# uBraids_SE_Display_Module.net
KiCad netlist of a schematic drawn in EAGLE
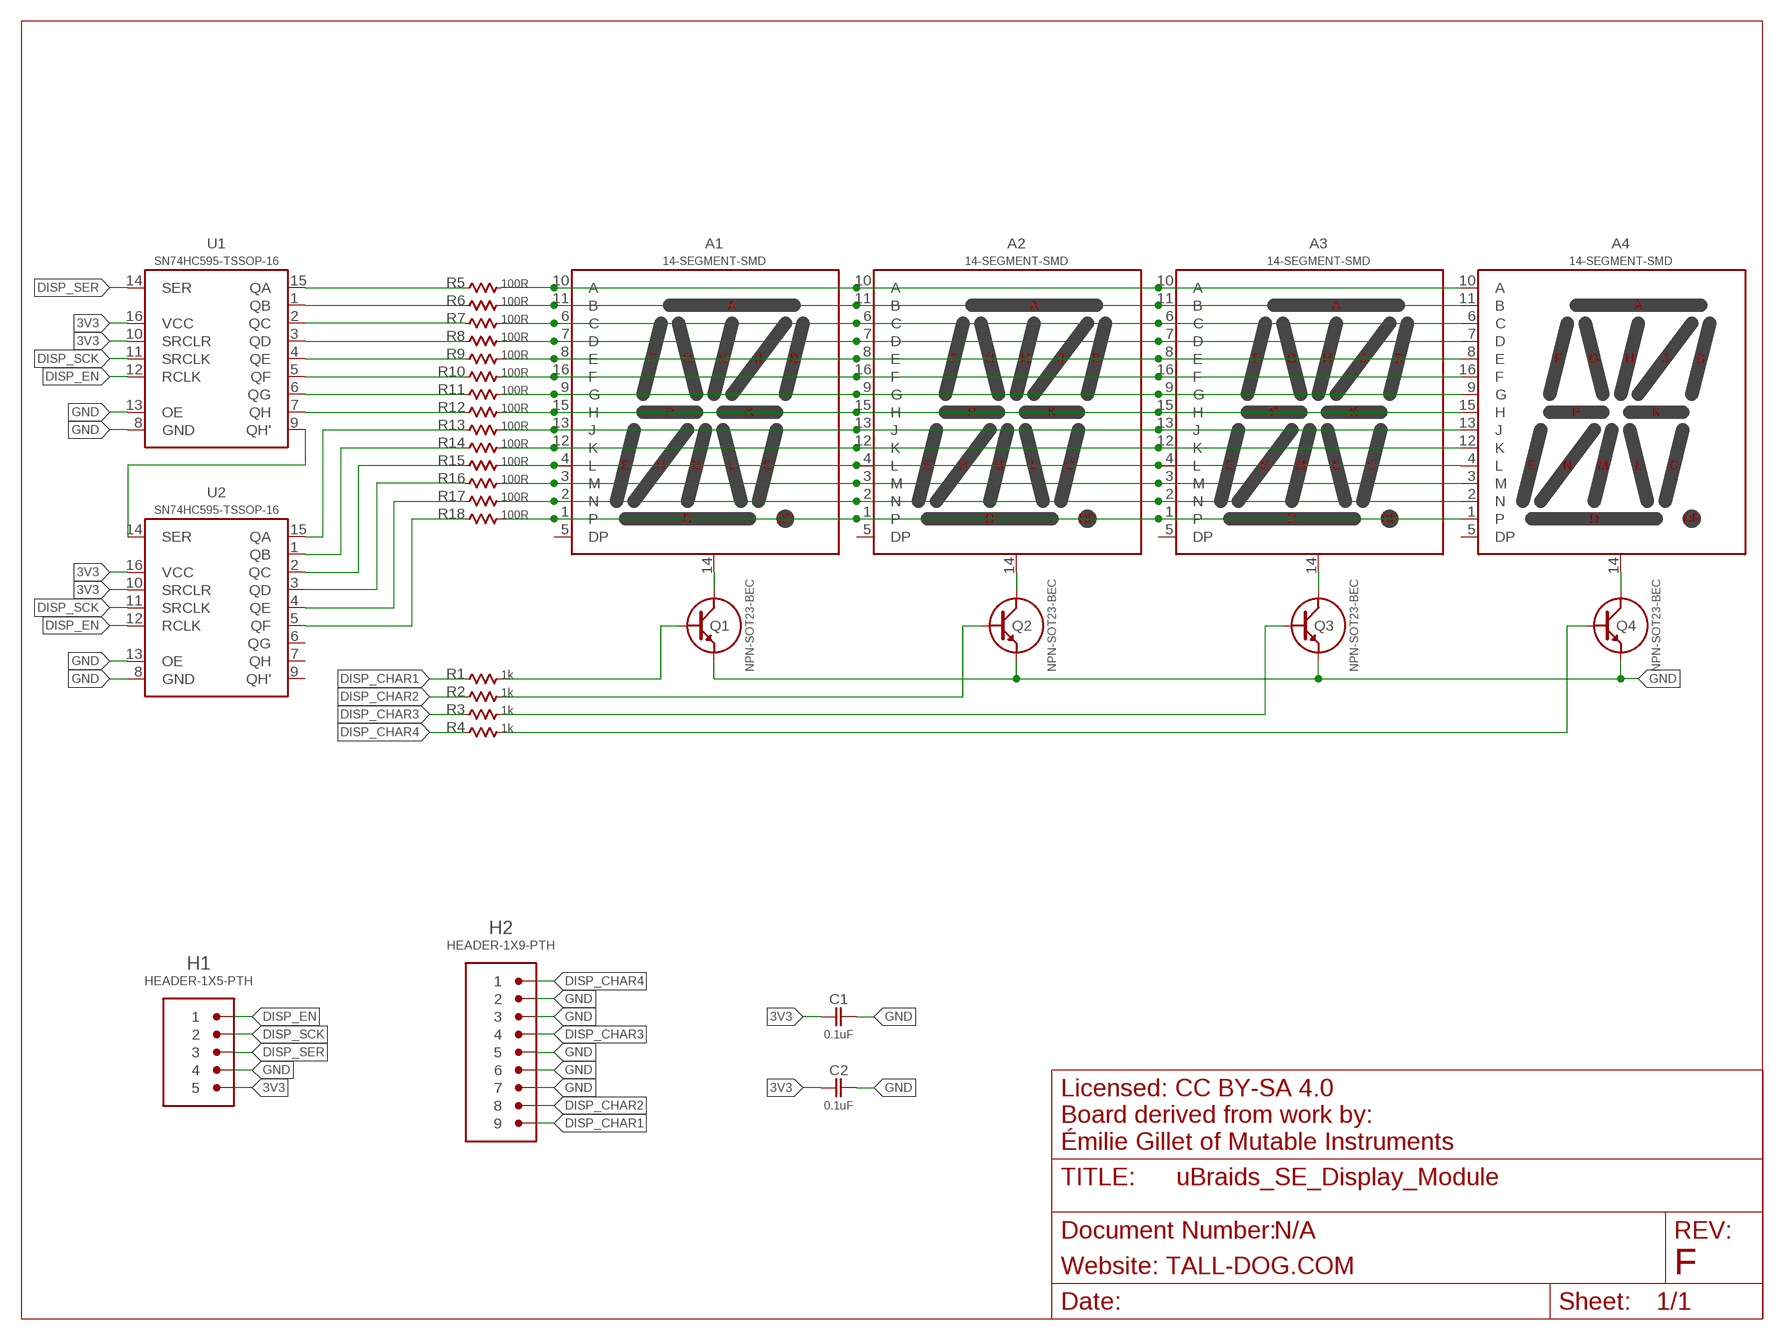
[diagram p0: schematic, sheet 1]

(export (version "E")
  (design (tool "Eeschema 10.0.6"))
  (components
    (comp (ref "A1")
      (value "14-SEGMENT-SMD")
      (footprint "eagle-import:14-SEGMENT")
      (libsource (lib "eagle-import") (part "14-SEGMENT-SMD"))
    )
    (comp (ref "A2")
      (value "14-SEGMENT-SMD")
      (footprint "eagle-import:14-SEGMENT")
      (libsource (lib "eagle-import") (part "14-SEGMENT-SMD"))
    )
    (comp (ref "A3")
      (value "14-SEGMENT-SMD")
      (footprint "eagle-import:14-SEGMENT")
      (libsource (lib "eagle-import") (part "14-SEGMENT-SMD"))
    )
    (comp (ref "A4")
      (value "14-SEGMENT-SMD")
      (footprint "eagle-import:14-SEGMENT")
      (libsource (lib "eagle-import") (part "14-SEGMENT-SMD"))
    )
    (comp (ref "C1")
      (value "0.1uF")
      (footprint "eagle-import:0603-NP")
      (libsource (lib "eagle-import") (part "CAP-NP-0603"))
    )
    (comp (ref "C2")
      (value "0.1uF")
      (footprint "eagle-import:0603-NP")
      (libsource (lib "eagle-import") (part "CAP-NP-0603"))
    )
    (comp (ref "H1")
      (value "HEADER-1X5-PTH")
      (footprint "eagle-import:PTH-0.1-1X5")
      (libsource (lib "eagle-import") (part "HEADER-1X5-PTH"))
    )
    (comp (ref "H2")
      (value "HEADER-1X9-PTH")
      (footprint "eagle-import:PTH-0.1-1X9")
      (libsource (lib "eagle-import") (part "HEADER-1X9-PTH"))
    )
    (comp (ref "Q1")
      (value "NPN-SOT23-BEC")
      (footprint "eagle-import:SOT-23")
      (libsource (lib "eagle-import") (part "NPN-SOT23-BEC"))
    )
    (comp (ref "Q2")
      (value "NPN-SOT23-BEC")
      (footprint "eagle-import:SOT-23")
      (libsource (lib "eagle-import") (part "NPN-SOT23-BEC"))
    )
    (comp (ref "Q3")
      (value "NPN-SOT23-BEC")
      (footprint "eagle-import:SOT-23")
      (libsource (lib "eagle-import") (part "NPN-SOT23-BEC"))
    )
    (comp (ref "Q4")
      (value "NPN-SOT23-BEC")
      (footprint "eagle-import:SOT-23")
      (libsource (lib "eagle-import") (part "NPN-SOT23-BEC"))
    )
    (comp (ref "R1")
      (value "1k")
      (footprint "eagle-import:0603-NP")
      (libsource (lib "eagle-import") (part "RESISTOR-0603"))
    )
    (comp (ref "R2")
      (value "1k")
      (footprint "eagle-import:0603-NP")
      (libsource (lib "eagle-import") (part "RESISTOR-0603"))
    )
    (comp (ref "R3")
      (value "1k")
      (footprint "eagle-import:0603-NP")
      (libsource (lib "eagle-import") (part "RESISTOR-0603"))
    )
    (comp (ref "R4")
      (value "1k")
      (footprint "eagle-import:0603-NP")
      (libsource (lib "eagle-import") (part "RESISTOR-0603"))
    )
    (comp (ref "R5")
      (value "100R")
      (footprint "eagle-import:0603-NP")
      (libsource (lib "eagle-import") (part "RESISTOR-0603"))
    )
    (comp (ref "R6")
      (value "100R")
      (footprint "eagle-import:0603-NP")
      (libsource (lib "eagle-import") (part "RESISTOR-0603"))
    )
    (comp (ref "R7")
      (value "100R")
      (footprint "eagle-import:0603-NP")
      (libsource (lib "eagle-import") (part "RESISTOR-0603"))
    )
    (comp (ref "R8")
      (value "100R")
      (footprint "eagle-import:0603-NP")
      (libsource (lib "eagle-import") (part "RESISTOR-0603"))
    )
    (comp (ref "R9")
      (value "100R")
      (footprint "eagle-import:0603-NP")
      (libsource (lib "eagle-import") (part "RESISTOR-0603"))
    )
    (comp (ref "R10")
      (value "100R")
      (footprint "eagle-import:0603-NP")
      (libsource (lib "eagle-import") (part "RESISTOR-0603"))
    )
    (comp (ref "R11")
      (value "100R")
      (footprint "eagle-import:0603-NP")
      (libsource (lib "eagle-import") (part "RESISTOR-0603"))
    )
    (comp (ref "R12")
      (value "100R")
      (footprint "eagle-import:0603-NP")
      (libsource (lib "eagle-import") (part "RESISTOR-0603"))
    )
    (comp (ref "R13")
      (value "100R")
      (footprint "eagle-import:0603-NP")
      (libsource (lib "eagle-import") (part "RESISTOR-0603"))
    )
    (comp (ref "R14")
      (value "100R")
      (footprint "eagle-import:0603-NP")
      (libsource (lib "eagle-import") (part "RESISTOR-0603"))
    )
    (comp (ref "R15")
      (value "100R")
      (footprint "eagle-import:0603-NP")
      (libsource (lib "eagle-import") (part "RESISTOR-0603"))
    )
    (comp (ref "R16")
      (value "100R")
      (footprint "eagle-import:0603-NP")
      (libsource (lib "eagle-import") (part "RESISTOR-0603"))
    )
    (comp (ref "R17")
      (value "100R")
      (footprint "eagle-import:0603-NP")
      (libsource (lib "eagle-import") (part "RESISTOR-0603"))
    )
    (comp (ref "R18")
      (value "100R")
      (footprint "eagle-import:0603-NP")
      (libsource (lib "eagle-import") (part "RESISTOR-0603"))
    )
    (comp (ref "U1")
      (value "SN74HC595-TSSOP-16")
      (footprint "eagle-import:TSSOP-16")
      (libsource (lib "eagle-import") (part "SN74HC595-TSSOP-16"))
    )
    (comp (ref "U2")
      (value "SN74HC595-TSSOP-16")
      (footprint "eagle-import:TSSOP-16")
      (libsource (lib "eagle-import") (part "SN74HC595-TSSOP-16"))
    )
  )
  (nets
    (net (code "1") (name "3V3") (class "Default")
      (node (ref "C1") (pin "1") (pinfunction "1_1") (pintype "bidirectional"))
      (node (ref "C2") (pin "1") (pinfunction "1_1") (pintype "bidirectional"))
      (node (ref "H1") (pin "5") (pinfunction "5_5") (pintype "bidirectional"))
      (node (ref "U1") (pin "10") (pinfunction "SRCLR_10") (pintype "bidirectional"))
      (node (ref "U1") (pin "16") (pinfunction "VCC_16") (pintype "bidirectional"))
      (node (ref "U2") (pin "10") (pinfunction "SRCLR_10") (pintype "bidirectional"))
      (node (ref "U2") (pin "16") (pinfunction "VCC_16") (pintype "bidirectional"))
    )
    (net (code "2") (name "DISP_CHAR1") (class "Default")
      (node (ref "H2") (pin "9") (pinfunction "9_9") (pintype "bidirectional"))
      (node (ref "R1") (pin "1") (pinfunction "1_1") (pintype "passive"))
    )
    (net (code "3") (name "DISP_CHAR2") (class "Default")
      (node (ref "H2") (pin "8") (pinfunction "8_8") (pintype "bidirectional"))
      (node (ref "R2") (pin "1") (pinfunction "1_1") (pintype "passive"))
    )
    (net (code "4") (name "DISP_CHAR3") (class "Default")
      (node (ref "H2") (pin "4") (pinfunction "4_4") (pintype "bidirectional"))
      (node (ref "R3") (pin "1") (pinfunction "1_1") (pintype "passive"))
    )
    (net (code "5") (name "DISP_CHAR4") (class "Default")
      (node (ref "H2") (pin "1") (pinfunction "1_1") (pintype "bidirectional"))
      (node (ref "R4") (pin "1") (pinfunction "1_1") (pintype "passive"))
    )
    (net (code "6") (name "DISP_EN") (class "Default")
      (node (ref "H1") (pin "1") (pinfunction "1_1") (pintype "bidirectional"))
      (node (ref "U1") (pin "12") (pinfunction "RCLK_12") (pintype "bidirectional"))
      (node (ref "U2") (pin "12") (pinfunction "RCLK_12") (pintype "bidirectional"))
    )
    (net (code "7") (name "DISP_SCK") (class "Default")
      (node (ref "H1") (pin "2") (pinfunction "2_2") (pintype "bidirectional"))
      (node (ref "U1") (pin "11") (pinfunction "SRCLK_11") (pintype "bidirectional"))
      (node (ref "U2") (pin "11") (pinfunction "SRCLK_11") (pintype "bidirectional"))
    )
    (net (code "8") (name "DISP_SER") (class "Default")
      (node (ref "H1") (pin "3") (pinfunction "3_3") (pintype "bidirectional"))
      (node (ref "U1") (pin "14") (pinfunction "SER_14") (pintype "bidirectional"))
    )
    (net (code "9") (name "GND") (class "Default")
      (node (ref "C1") (pin "2") (pinfunction "2_2") (pintype "bidirectional"))
      (node (ref "C2") (pin "2") (pinfunction "2_2") (pintype "bidirectional"))
      (node (ref "H1") (pin "4") (pinfunction "4_4") (pintype "bidirectional"))
      (node (ref "H2") (pin "2") (pinfunction "2_2") (pintype "bidirectional"))
      (node (ref "H2") (pin "3") (pinfunction "3_3") (pintype "bidirectional"))
      (node (ref "H2") (pin "5") (pinfunction "5_5") (pintype "bidirectional"))
      (node (ref "H2") (pin "6") (pinfunction "6_6") (pintype "bidirectional"))
      (node (ref "H2") (pin "7") (pinfunction "7_7") (pintype "bidirectional"))
      (node (ref "Q1") (pin "2") (pinfunction "E_2") (pintype "passive"))
      (node (ref "Q2") (pin "2") (pinfunction "E_2") (pintype "passive"))
      (node (ref "Q3") (pin "2") (pinfunction "E_2") (pintype "passive"))
      (node (ref "Q4") (pin "2") (pinfunction "E_2") (pintype "passive"))
      (node (ref "U1") (pin "13") (pinfunction "OE_13") (pintype "bidirectional"))
      (node (ref "U1") (pin "8") (pinfunction "GND_8") (pintype "bidirectional"))
      (node (ref "U2") (pin "13") (pinfunction "OE_13") (pintype "bidirectional"))
      (node (ref "U2") (pin "8") (pinfunction "GND_8") (pintype "bidirectional"))
    )
    (net (code "10") (name "Net-(A1-A)") (class "Default")
      (node (ref "A1") (pin "10") (pinfunction "A_10") (pintype "bidirectional"))
      (node (ref "A2") (pin "10") (pinfunction "A_10") (pintype "bidirectional"))
      (node (ref "A3") (pin "10") (pinfunction "A_10") (pintype "bidirectional"))
      (node (ref "A4") (pin "10") (pinfunction "A_10") (pintype "bidirectional"))
      (node (ref "R5") (pin "2") (pinfunction "2_2") (pintype "passive"))
    )
    (net (code "11") (name "Net-(A1-B)") (class "Default")
      (node (ref "A1") (pin "11") (pinfunction "B_11") (pintype "bidirectional"))
      (node (ref "A2") (pin "11") (pinfunction "B_11") (pintype "bidirectional"))
      (node (ref "A3") (pin "11") (pinfunction "B_11") (pintype "bidirectional"))
      (node (ref "A4") (pin "11") (pinfunction "B_11") (pintype "bidirectional"))
      (node (ref "R6") (pin "2") (pinfunction "2_2") (pintype "passive"))
    )
    (net (code "12") (name "Net-(A1-C)") (class "Default")
      (node (ref "A1") (pin "6") (pinfunction "C_6") (pintype "bidirectional"))
      (node (ref "A2") (pin "6") (pinfunction "C_6") (pintype "bidirectional"))
      (node (ref "A3") (pin "6") (pinfunction "C_6") (pintype "bidirectional"))
      (node (ref "A4") (pin "6") (pinfunction "C_6") (pintype "bidirectional"))
      (node (ref "R7") (pin "2") (pinfunction "2_2") (pintype "passive"))
    )
    (net (code "13") (name "Net-(A1-CATHODE)") (class "Default")
      (node (ref "A1") (pin "14") (pinfunction "CATHODE_14") (pintype "bidirectional"))
      (node (ref "Q1") (pin "3") (pinfunction "C_3") (pintype "passive"))
    )
    (net (code "14") (name "Net-(A1-D)") (class "Default")
      (node (ref "A1") (pin "7") (pinfunction "D_7") (pintype "bidirectional"))
      (node (ref "A2") (pin "7") (pinfunction "D_7") (pintype "bidirectional"))
      (node (ref "A3") (pin "7") (pinfunction "D_7") (pintype "bidirectional"))
      (node (ref "A4") (pin "7") (pinfunction "D_7") (pintype "bidirectional"))
      (node (ref "R8") (pin "2") (pinfunction "2_2") (pintype "passive"))
    )
    (net (code "15") (name "Net-(A1-E)") (class "Default")
      (node (ref "A1") (pin "8") (pinfunction "E_8") (pintype "bidirectional"))
      (node (ref "A2") (pin "8") (pinfunction "E_8") (pintype "bidirectional"))
      (node (ref "A3") (pin "8") (pinfunction "E_8") (pintype "bidirectional"))
      (node (ref "A4") (pin "8") (pinfunction "E_8") (pintype "bidirectional"))
      (node (ref "R9") (pin "2") (pinfunction "2_2") (pintype "passive"))
    )
    (net (code "16") (name "Net-(A1-F)") (class "Default")
      (node (ref "A1") (pin "16") (pinfunction "F_16") (pintype "bidirectional"))
      (node (ref "A2") (pin "16") (pinfunction "F_16") (pintype "bidirectional"))
      (node (ref "A3") (pin "16") (pinfunction "F_16") (pintype "bidirectional"))
      (node (ref "A4") (pin "16") (pinfunction "F_16") (pintype "bidirectional"))
      (node (ref "R10") (pin "2") (pinfunction "2_2") (pintype "passive"))
    )
    (net (code "17") (name "Net-(A1-G)") (class "Default")
      (node (ref "A1") (pin "9") (pinfunction "G_9") (pintype "bidirectional"))
      (node (ref "A2") (pin "9") (pinfunction "G_9") (pintype "bidirectional"))
      (node (ref "A3") (pin "9") (pinfunction "G_9") (pintype "bidirectional"))
      (node (ref "A4") (pin "9") (pinfunction "G_9") (pintype "bidirectional"))
      (node (ref "R11") (pin "2") (pinfunction "2_2") (pintype "passive"))
    )
    (net (code "18") (name "Net-(A1-H)") (class "Default")
      (node (ref "A1") (pin "15") (pinfunction "H_15") (pintype "bidirectional"))
      (node (ref "A2") (pin "15") (pinfunction "H_15") (pintype "bidirectional"))
      (node (ref "A3") (pin "15") (pinfunction "H_15") (pintype "bidirectional"))
      (node (ref "A4") (pin "15") (pinfunction "H_15") (pintype "bidirectional"))
      (node (ref "R12") (pin "2") (pinfunction "2_2") (pintype "passive"))
    )
    (net (code "19") (name "Net-(A1-J)") (class "Default")
      (node (ref "A1") (pin "13") (pinfunction "J_13") (pintype "bidirectional"))
      (node (ref "A2") (pin "13") (pinfunction "J_13") (pintype "bidirectional"))
      (node (ref "A3") (pin "13") (pinfunction "J_13") (pintype "bidirectional"))
      (node (ref "A4") (pin "13") (pinfunction "J_13") (pintype "bidirectional"))
      (node (ref "R13") (pin "2") (pinfunction "2_2") (pintype "passive"))
    )
    (net (code "20") (name "Net-(A1-K)") (class "Default")
      (node (ref "A1") (pin "12") (pinfunction "K_12") (pintype "bidirectional"))
      (node (ref "A2") (pin "12") (pinfunction "K_12") (pintype "bidirectional"))
      (node (ref "A3") (pin "12") (pinfunction "K_12") (pintype "bidirectional"))
      (node (ref "A4") (pin "12") (pinfunction "K_12") (pintype "bidirectional"))
      (node (ref "R14") (pin "2") (pinfunction "2_2") (pintype "passive"))
    )
    (net (code "21") (name "Net-(A1-L)") (class "Default")
      (node (ref "A1") (pin "4") (pinfunction "L_4") (pintype "bidirectional"))
      (node (ref "A2") (pin "4") (pinfunction "L_4") (pintype "bidirectional"))
      (node (ref "A3") (pin "4") (pinfunction "L_4") (pintype "bidirectional"))
      (node (ref "A4") (pin "4") (pinfunction "L_4") (pintype "bidirectional"))
      (node (ref "R15") (pin "2") (pinfunction "2_2") (pintype "passive"))
    )
    (net (code "22") (name "Net-(A1-M)") (class "Default")
      (node (ref "A1") (pin "3") (pinfunction "M_3") (pintype "bidirectional"))
      (node (ref "A2") (pin "3") (pinfunction "M_3") (pintype "bidirectional"))
      (node (ref "A3") (pin "3") (pinfunction "M_3") (pintype "bidirectional"))
      (node (ref "A4") (pin "3") (pinfunction "M_3") (pintype "bidirectional"))
      (node (ref "R16") (pin "2") (pinfunction "2_2") (pintype "passive"))
    )
    (net (code "23") (name "Net-(A1-N)") (class "Default")
      (node (ref "A1") (pin "2") (pinfunction "N_2") (pintype "bidirectional"))
      (node (ref "A2") (pin "2") (pinfunction "N_2") (pintype "bidirectional"))
      (node (ref "A3") (pin "2") (pinfunction "N_2") (pintype "bidirectional"))
      (node (ref "A4") (pin "2") (pinfunction "N_2") (pintype "bidirectional"))
      (node (ref "R17") (pin "2") (pinfunction "2_2") (pintype "passive"))
    )
    (net (code "24") (name "Net-(A1-P)") (class "Default")
      (node (ref "A1") (pin "1") (pinfunction "P_1") (pintype "bidirectional"))
      (node (ref "A2") (pin "1") (pinfunction "P_1") (pintype "bidirectional"))
      (node (ref "A3") (pin "1") (pinfunction "P_1") (pintype "bidirectional"))
      (node (ref "A4") (pin "1") (pinfunction "P_1") (pintype "bidirectional"))
      (node (ref "R18") (pin "2") (pinfunction "2_2") (pintype "passive"))
    )
    (net (code "25") (name "Net-(A2-CATHODE)") (class "Default")
      (node (ref "A2") (pin "14") (pinfunction "CATHODE_14") (pintype "bidirectional"))
      (node (ref "Q2") (pin "3") (pinfunction "C_3") (pintype "passive"))
    )
    (net (code "26") (name "Net-(A3-CATHODE)") (class "Default")
      (node (ref "A3") (pin "14") (pinfunction "CATHODE_14") (pintype "bidirectional"))
      (node (ref "Q3") (pin "3") (pinfunction "C_3") (pintype "passive"))
    )
    (net (code "27") (name "Net-(A4-CATHODE)") (class "Default")
      (node (ref "A4") (pin "14") (pinfunction "CATHODE_14") (pintype "bidirectional"))
      (node (ref "Q4") (pin "3") (pinfunction "C_3") (pintype "passive"))
    )
    (net (code "28") (name "Net-(Q1-B)") (class "Default")
      (node (ref "Q1") (pin "1") (pinfunction "B_1") (pintype "passive"))
      (node (ref "R1") (pin "2") (pinfunction "2_2") (pintype "passive"))
    )
    (net (code "29") (name "Net-(Q2-B)") (class "Default")
      (node (ref "Q2") (pin "1") (pinfunction "B_1") (pintype "passive"))
      (node (ref "R2") (pin "2") (pinfunction "2_2") (pintype "passive"))
    )
    (net (code "30") (name "Net-(Q3-B)") (class "Default")
      (node (ref "Q3") (pin "1") (pinfunction "B_1") (pintype "passive"))
      (node (ref "R3") (pin "2") (pinfunction "2_2") (pintype "passive"))
    )
    (net (code "31") (name "Net-(Q4-B)") (class "Default")
      (node (ref "Q4") (pin "1") (pinfunction "B_1") (pintype "passive"))
      (node (ref "R4") (pin "2") (pinfunction "2_2") (pintype "passive"))
    )
    (net (code "32") (name "Net-(U1-QA)") (class "Default")
      (node (ref "R5") (pin "1") (pinfunction "1_1") (pintype "passive"))
      (node (ref "U1") (pin "15") (pinfunction "QA_15") (pintype "bidirectional"))
    )
    (net (code "33") (name "Net-(U1-QB)") (class "Default")
      (node (ref "R6") (pin "1") (pinfunction "1_1") (pintype "passive"))
      (node (ref "U1") (pin "1") (pinfunction "QB_1") (pintype "bidirectional"))
    )
    (net (code "34") (name "Net-(U1-QC)") (class "Default")
      (node (ref "R7") (pin "1") (pinfunction "1_1") (pintype "passive"))
      (node (ref "U1") (pin "2") (pinfunction "QC_2") (pintype "bidirectional"))
    )
    (net (code "35") (name "Net-(U1-QD)") (class "Default")
      (node (ref "R8") (pin "1") (pinfunction "1_1") (pintype "passive"))
      (node (ref "U1") (pin "3") (pinfunction "QD_3") (pintype "bidirectional"))
    )
    (net (code "36") (name "Net-(U1-QE)") (class "Default")
      (node (ref "R9") (pin "1") (pinfunction "1_1") (pintype "passive"))
      (node (ref "U1") (pin "4") (pinfunction "QE_4") (pintype "bidirectional"))
    )
    (net (code "37") (name "Net-(U1-QF)") (class "Default")
      (node (ref "R10") (pin "1") (pinfunction "1_1") (pintype "passive"))
      (node (ref "U1") (pin "5") (pinfunction "QF_5") (pintype "bidirectional"))
    )
    (net (code "38") (name "Net-(U1-QG)") (class "Default")
      (node (ref "R11") (pin "1") (pinfunction "1_1") (pintype "passive"))
      (node (ref "U1") (pin "6") (pinfunction "QG_6") (pintype "bidirectional"))
    )
    (net (code "39") (name "Net-(U1-QH')") (class "Default")
      (node (ref "U1") (pin "9") (pinfunction "QH'_9") (pintype "bidirectional"))
      (node (ref "U2") (pin "14") (pinfunction "SER_14") (pintype "bidirectional"))
    )
    (net (code "40") (name "Net-(U1-QH)") (class "Default")
      (node (ref "R12") (pin "1") (pinfunction "1_1") (pintype "passive"))
      (node (ref "U1") (pin "7") (pinfunction "QH_7") (pintype "bidirectional"))
    )
    (net (code "41") (name "Net-(U2-QA)") (class "Default")
      (node (ref "R13") (pin "1") (pinfunction "1_1") (pintype "passive"))
      (node (ref "U2") (pin "15") (pinfunction "QA_15") (pintype "bidirectional"))
    )
    (net (code "42") (name "Net-(U2-QB)") (class "Default")
      (node (ref "R14") (pin "1") (pinfunction "1_1") (pintype "passive"))
      (node (ref "U2") (pin "1") (pinfunction "QB_1") (pintype "bidirectional"))
    )
    (net (code "43") (name "Net-(U2-QC)") (class "Default")
      (node (ref "R15") (pin "1") (pinfunction "1_1") (pintype "passive"))
      (node (ref "U2") (pin "2") (pinfunction "QC_2") (pintype "bidirectional"))
    )
    (net (code "44") (name "Net-(U2-QD)") (class "Default")
      (node (ref "R16") (pin "1") (pinfunction "1_1") (pintype "passive"))
      (node (ref "U2") (pin "3") (pinfunction "QD_3") (pintype "bidirectional"))
    )
    (net (code "45") (name "Net-(U2-QE)") (class "Default")
      (node (ref "R17") (pin "1") (pinfunction "1_1") (pintype "passive"))
      (node (ref "U2") (pin "4") (pinfunction "QE_4") (pintype "bidirectional"))
    )
    (net (code "46") (name "Net-(U2-QF)") (class "Default")
      (node (ref "R18") (pin "1") (pinfunction "1_1") (pintype "passive"))
      (node (ref "U2") (pin "5") (pinfunction "QF_5") (pintype "bidirectional"))
    )
    (net (code "47") (name "unconnected-(A1-DP-Pad5)") (class "Default")
      (node (ref "A1") (pin "5") (pinfunction "DP_5") (pintype "bidirectional"))
    )
    (net (code "48") (name "unconnected-(A2-DP-Pad5)") (class "Default")
      (node (ref "A2") (pin "5") (pinfunction "DP_5") (pintype "bidirectional"))
    )
    (net (code "49") (name "unconnected-(A3-DP-Pad5)") (class "Default")
      (node (ref "A3") (pin "5") (pinfunction "DP_5") (pintype "bidirectional"))
    )
    (net (code "50") (name "unconnected-(A4-DP-Pad5)") (class "Default")
      (node (ref "A4") (pin "5") (pinfunction "DP_5") (pintype "bidirectional"))
    )
    (net (code "51") (name "unconnected-(U2-QG-Pad6)") (class "Default")
      (node (ref "U2") (pin "6") (pinfunction "QG_6") (pintype "bidirectional"))
    )
    (net (code "52") (name "unconnected-(U2-QH'-Pad9)") (class "Default")
      (node (ref "U2") (pin "9") (pinfunction "QH'_9") (pintype "bidirectional"))
    )
    (net (code "53") (name "unconnected-(U2-QH-Pad7)") (class "Default")
      (node (ref "U2") (pin "7") (pinfunction "QH_7") (pintype "bidirectional"))
    )
  )
)
